# PGTNX01_teensy.net
KiCad netlist of a schematic drawn in EAGLE
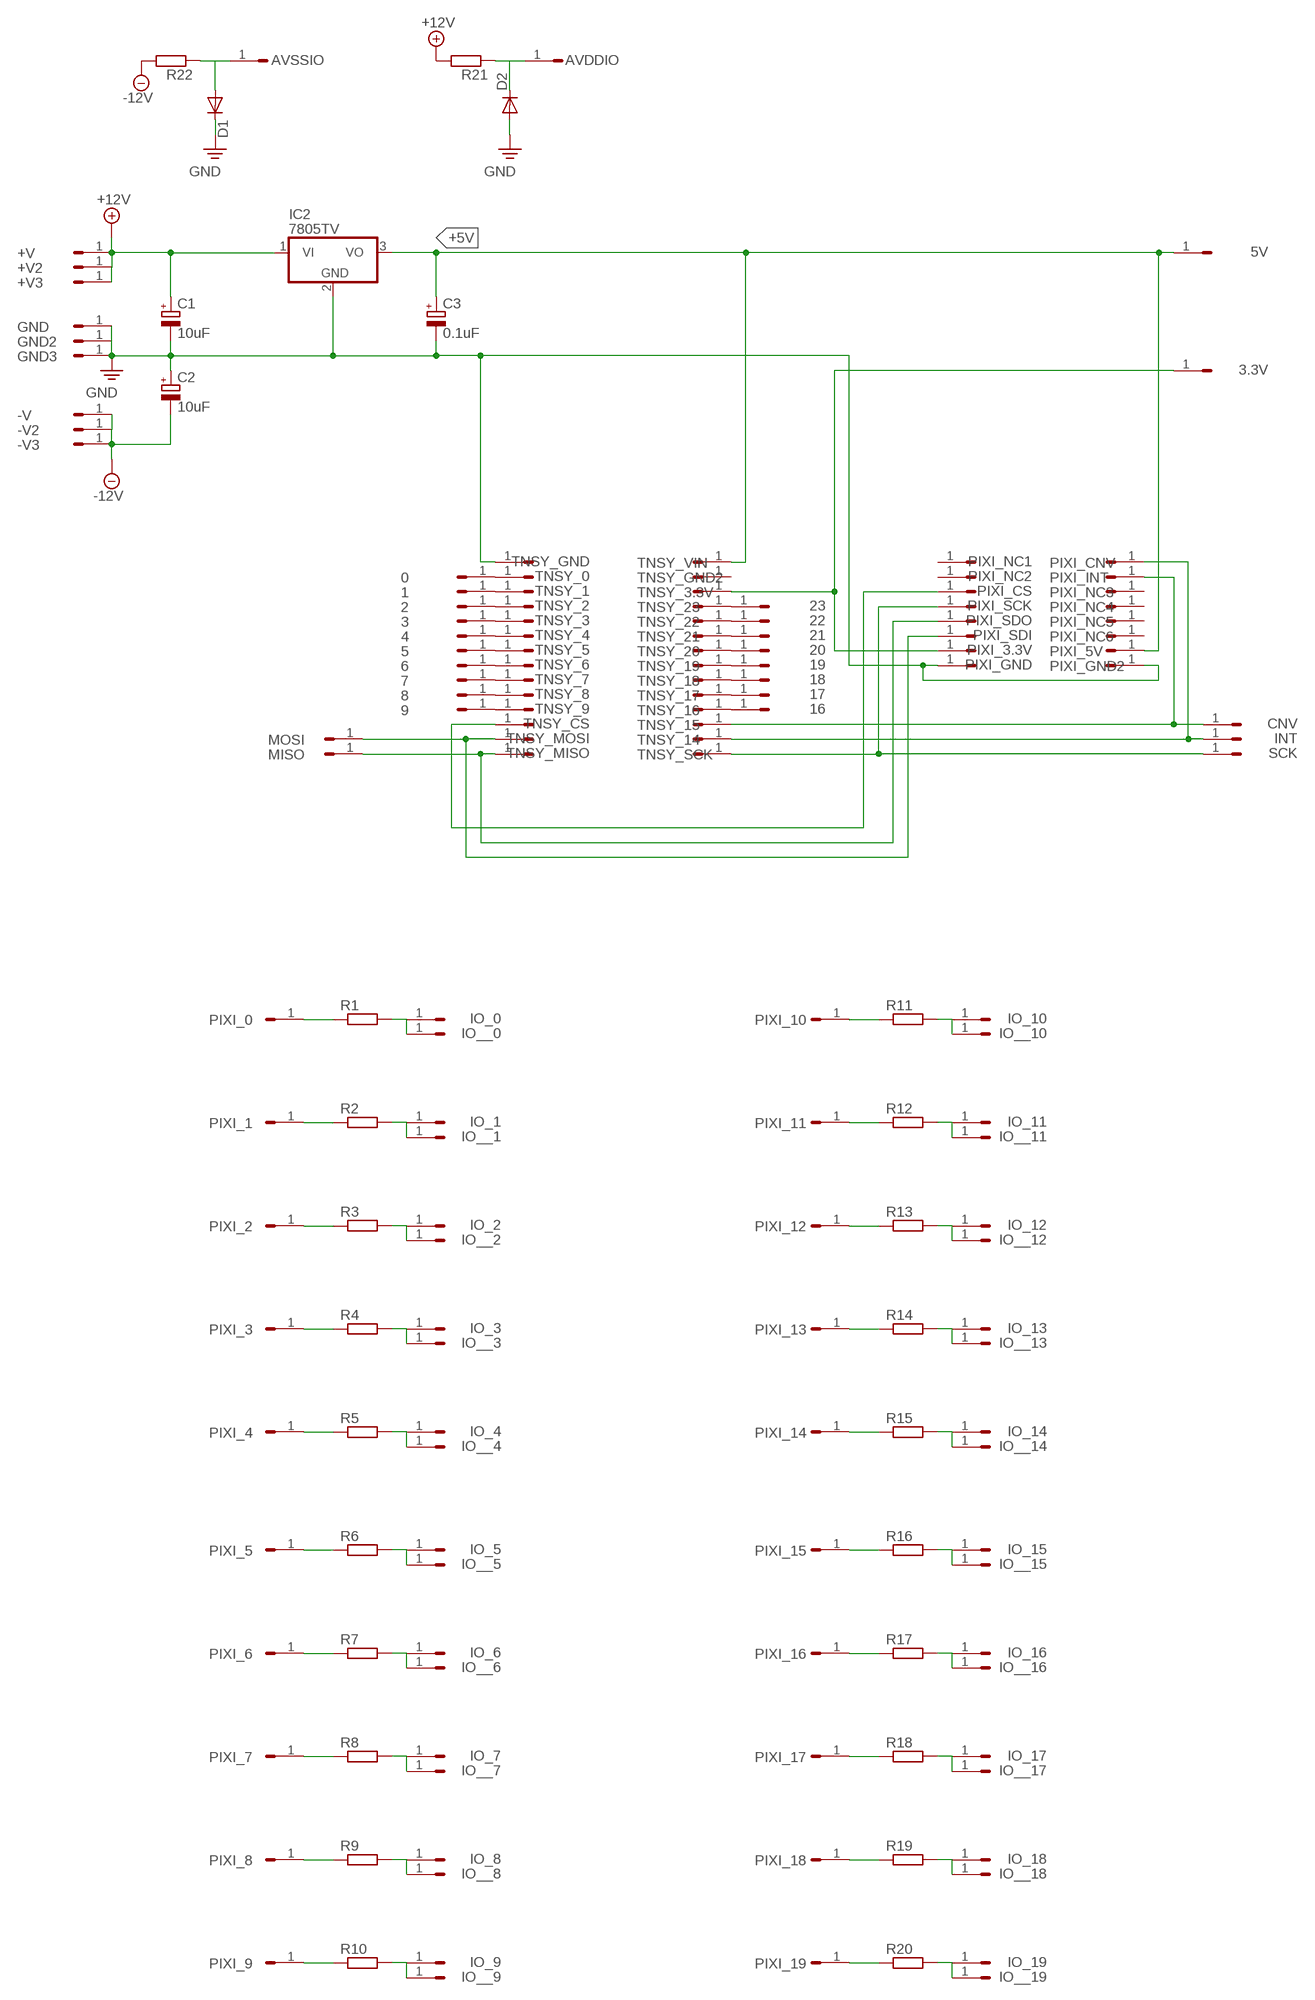
[diagram p0: schematic, sheet 1]

(export (version "E")
  (design (tool "Eeschema 10.0.6"))
  (components
    (comp (ref "+V")
      (value "HEADER/MALE/01")
      (footprint "eagle-import:HEADER_MALE_01")
      (fields (field (name "SPICEPREFIX") "X"))
      (libsource (lib "eagle-import") (part "HEADER/MALE/01"))
    )
    (comp (ref "+V2")
      (value "HEADER/MALE/01")
      (footprint "eagle-import:HEADER_MALE_01")
      (fields (field (name "SPICEPREFIX") "X"))
      (libsource (lib "eagle-import") (part "HEADER/MALE/01"))
    )
    (comp (ref "+V3")
      (value "HEADER/MALE/01")
      (footprint "eagle-import:HEADER_MALE_01")
      (fields (field (name "SPICEPREFIX") "X"))
      (libsource (lib "eagle-import") (part "HEADER/MALE/01"))
    )
    (comp (ref "-V")
      (value "HEADER/MALE/01")
      (footprint "eagle-import:HEADER_MALE_01")
      (fields (field (name "SPICEPREFIX") "X"))
      (libsource (lib "eagle-import") (part "HEADER/MALE/01"))
    )
    (comp (ref "-V2")
      (value "HEADER/MALE/01")
      (footprint "eagle-import:HEADER_MALE_01")
      (fields (field (name "SPICEPREFIX") "X"))
      (libsource (lib "eagle-import") (part "HEADER/MALE/01"))
    )
    (comp (ref "-V3")
      (value "HEADER/MALE/01")
      (footprint "eagle-import:HEADER_MALE_01")
      (fields (field (name "SPICEPREFIX") "X"))
      (libsource (lib "eagle-import") (part "HEADER/MALE/01"))
    )
    (comp (ref "0")
      (value "HEADER/MALE/01")
      (footprint "eagle-import:HEADER_MALE_01")
      (fields (field (name "SPICEPREFIX") "X"))
      (libsource (lib "eagle-import") (part "HEADER/MALE/01"))
    )
    (comp (ref "1")
      (value "HEADER/MALE/01")
      (footprint "eagle-import:HEADER_MALE_01")
      (fields (field (name "SPICEPREFIX") "X"))
      (libsource (lib "eagle-import") (part "HEADER/MALE/01"))
    )
    (comp (ref "2")
      (value "HEADER/MALE/01")
      (footprint "eagle-import:HEADER_MALE_01")
      (fields (field (name "SPICEPREFIX") "X"))
      (libsource (lib "eagle-import") (part "HEADER/MALE/01"))
    )
    (comp (ref "3")
      (value "HEADER/MALE/01")
      (footprint "eagle-import:HEADER_MALE_01")
      (fields (field (name "SPICEPREFIX") "X"))
      (libsource (lib "eagle-import") (part "HEADER/MALE/01"))
    )
    (comp (ref "3.3V")
      (value "HEADER/MALE/01")
      (footprint "eagle-import:HEADER_MALE_01")
      (fields (field (name "SPICEPREFIX") "X"))
      (libsource (lib "eagle-import") (part "HEADER/MALE/01"))
    )
    (comp (ref "4")
      (value "HEADER/MALE/01")
      (footprint "eagle-import:HEADER_MALE_01")
      (fields (field (name "SPICEPREFIX") "X"))
      (libsource (lib "eagle-import") (part "HEADER/MALE/01"))
    )
    (comp (ref "5")
      (value "HEADER/MALE/01")
      (footprint "eagle-import:HEADER_MALE_01")
      (fields (field (name "SPICEPREFIX") "X"))
      (libsource (lib "eagle-import") (part "HEADER/MALE/01"))
    )
    (comp (ref "5V")
      (value "HEADER/MALE/01")
      (footprint "eagle-import:HEADER_MALE_01")
      (fields (field (name "SPICEPREFIX") "X"))
      (libsource (lib "eagle-import") (part "HEADER/MALE/01"))
    )
    (comp (ref "6")
      (value "HEADER/MALE/01")
      (footprint "eagle-import:HEADER_MALE_01")
      (fields (field (name "SPICEPREFIX") "X"))
      (libsource (lib "eagle-import") (part "HEADER/MALE/01"))
    )
    (comp (ref "7")
      (value "HEADER/MALE/01")
      (footprint "eagle-import:HEADER_MALE_01")
      (fields (field (name "SPICEPREFIX") "X"))
      (libsource (lib "eagle-import") (part "HEADER/MALE/01"))
    )
    (comp (ref "8")
      (value "HEADER/MALE/01")
      (footprint "eagle-import:HEADER_MALE_01")
      (fields (field (name "SPICEPREFIX") "X"))
      (libsource (lib "eagle-import") (part "HEADER/MALE/01"))
    )
    (comp (ref "9")
      (value "HEADER/MALE/01")
      (footprint "eagle-import:HEADER_MALE_01")
      (fields (field (name "SPICEPREFIX") "X"))
      (libsource (lib "eagle-import") (part "HEADER/MALE/01"))
    )
    (comp (ref "16")
      (value "HEADER/MALE/01")
      (footprint "eagle-import:HEADER_MALE_01")
      (fields (field (name "SPICEPREFIX") "X"))
      (libsource (lib "eagle-import") (part "HEADER/MALE/01"))
    )
    (comp (ref "17")
      (value "HEADER/MALE/01")
      (footprint "eagle-import:HEADER_MALE_01")
      (fields (field (name "SPICEPREFIX") "X"))
      (libsource (lib "eagle-import") (part "HEADER/MALE/01"))
    )
    (comp (ref "18")
      (value "HEADER/MALE/01")
      (footprint "eagle-import:HEADER_MALE_01")
      (fields (field (name "SPICEPREFIX") "X"))
      (libsource (lib "eagle-import") (part "HEADER/MALE/01"))
    )
    (comp (ref "19")
      (value "HEADER/MALE/01")
      (footprint "eagle-import:HEADER_MALE_01")
      (fields (field (name "SPICEPREFIX") "X"))
      (libsource (lib "eagle-import") (part "HEADER/MALE/01"))
    )
    (comp (ref "20")
      (value "HEADER/MALE/01")
      (footprint "eagle-import:HEADER_MALE_01")
      (fields (field (name "SPICEPREFIX") "X"))
      (libsource (lib "eagle-import") (part "HEADER/MALE/01"))
    )
    (comp (ref "21")
      (value "HEADER/MALE/01")
      (footprint "eagle-import:HEADER_MALE_01")
      (fields (field (name "SPICEPREFIX") "X"))
      (libsource (lib "eagle-import") (part "HEADER/MALE/01"))
    )
    (comp (ref "22")
      (value "HEADER/MALE/01")
      (footprint "eagle-import:HEADER_MALE_01")
      (fields (field (name "SPICEPREFIX") "X"))
      (libsource (lib "eagle-import") (part "HEADER/MALE/01"))
    )
    (comp (ref "23")
      (value "HEADER/MALE/01")
      (footprint "eagle-import:HEADER_MALE_01")
      (fields (field (name "SPICEPREFIX") "X"))
      (libsource (lib "eagle-import") (part "HEADER/MALE/01"))
    )
    (comp (ref "AVDDIO")
      (value "HEADER/MALE/01")
      (footprint "eagle-import:HEADER_MALE_01")
      (fields (field (name "SPICEPREFIX") "X"))
      (libsource (lib "eagle-import") (part "HEADER/MALE/01"))
    )
    (comp (ref "AVSSIO")
      (value "HEADER/MALE/01")
      (footprint "eagle-import:HEADER_MALE_01")
      (fields (field (name "SPICEPREFIX") "X"))
      (libsource (lib "eagle-import") (part "HEADER/MALE/01"))
    )
    (comp (ref "C1")
      (value "10uF")
      (footprint "eagle-import:E2,5-6")
      (fields (field (name "SPICEPREFIX") "C"))
      (libsource (lib "eagle-import") (part "CAPACITOR/POLARIZEDE2.5-6"))
    )
    (comp (ref "C2")
      (value "10uF")
      (footprint "eagle-import:E2,5-6")
      (fields (field (name "SPICEPREFIX") "C"))
      (libsource (lib "eagle-import") (part "CAPACITOR/POLARIZEDE2.5-6"))
    )
    (comp (ref "C3")
      (value "0.1uF")
      (footprint "eagle-import:E2,5-6")
      (fields (field (name "SPICEPREFIX") "C"))
      (libsource (lib "eagle-import") (part "CAPACITOR/POLARIZEDE2.5-6"))
    )
    (comp (ref "CNV")
      (value "HEADER/MALE/01")
      (footprint "eagle-import:HEADER_MALE_01")
      (fields (field (name "SPICEPREFIX") "X"))
      (libsource (lib "eagle-import") (part "HEADER/MALE/01"))
    )
    (comp (ref "D1")
      (value "1N4148DO35-7")
      (footprint "eagle-import:DO35-7")
      (libsource (lib "eagle-import") (part "1N4148DO35-7"))
    )
    (comp (ref "D2")
      (value "1N4148DO35-7")
      (footprint "eagle-import:DO35-7")
      (libsource (lib "eagle-import") (part "1N4148DO35-7"))
    )
    (comp (ref "GND")
      (value "HEADER/MALE/01")
      (footprint "eagle-import:HEADER_MALE_01")
      (fields (field (name "SPICEPREFIX") "X"))
      (libsource (lib "eagle-import") (part "HEADER/MALE/01"))
    )
    (comp (ref "GND2")
      (value "HEADER/MALE/01")
      (footprint "eagle-import:HEADER_MALE_01")
      (fields (field (name "SPICEPREFIX") "X"))
      (libsource (lib "eagle-import") (part "HEADER/MALE/01"))
    )
    (comp (ref "GND3")
      (value "HEADER/MALE/01")
      (footprint "eagle-import:HEADER_MALE_01")
      (fields (field (name "SPICEPREFIX") "X"))
      (libsource (lib "eagle-import") (part "HEADER/MALE/01"))
    )
    (comp (ref "IC2")
      (value "7805TV")
      (footprint "eagle-import:TO220V")
      (libsource (lib "eagle-import") (part "78TV05"))
    )
    (comp (ref "INT")
      (value "HEADER/MALE/01")
      (footprint "eagle-import:HEADER_MALE_01")
      (fields (field (name "SPICEPREFIX") "X"))
      (libsource (lib "eagle-import") (part "HEADER/MALE/01"))
    )
    (comp (ref "IO_0")
      (value "HEADER/MALE/01")
      (footprint "eagle-import:HEADER_MALE_01")
      (fields (field (name "SPICEPREFIX") "X"))
      (libsource (lib "eagle-import") (part "HEADER/MALE/01"))
    )
    (comp (ref "IO_1")
      (value "HEADER/MALE/01")
      (footprint "eagle-import:HEADER_MALE_01")
      (fields (field (name "SPICEPREFIX") "X"))
      (libsource (lib "eagle-import") (part "HEADER/MALE/01"))
    )
    (comp (ref "IO_2")
      (value "HEADER/MALE/01")
      (footprint "eagle-import:HEADER_MALE_01")
      (fields (field (name "SPICEPREFIX") "X"))
      (libsource (lib "eagle-import") (part "HEADER/MALE/01"))
    )
    (comp (ref "IO_3")
      (value "HEADER/MALE/01")
      (footprint "eagle-import:HEADER_MALE_01")
      (fields (field (name "SPICEPREFIX") "X"))
      (libsource (lib "eagle-import") (part "HEADER/MALE/01"))
    )
    (comp (ref "IO_4")
      (value "HEADER/MALE/01")
      (footprint "eagle-import:HEADER_MALE_01")
      (fields (field (name "SPICEPREFIX") "X"))
      (libsource (lib "eagle-import") (part "HEADER/MALE/01"))
    )
    (comp (ref "IO_5")
      (value "HEADER/MALE/01")
      (footprint "eagle-import:HEADER_MALE_01")
      (fields (field (name "SPICEPREFIX") "X"))
      (libsource (lib "eagle-import") (part "HEADER/MALE/01"))
    )
    (comp (ref "IO_6")
      (value "HEADER/MALE/01")
      (footprint "eagle-import:HEADER_MALE_01")
      (fields (field (name "SPICEPREFIX") "X"))
      (libsource (lib "eagle-import") (part "HEADER/MALE/01"))
    )
    (comp (ref "IO_7")
      (value "HEADER/MALE/01")
      (footprint "eagle-import:HEADER_MALE_01")
      (fields (field (name "SPICEPREFIX") "X"))
      (libsource (lib "eagle-import") (part "HEADER/MALE/01"))
    )
    (comp (ref "IO_8")
      (value "HEADER/MALE/01")
      (footprint "eagle-import:HEADER_MALE_01")
      (fields (field (name "SPICEPREFIX") "X"))
      (libsource (lib "eagle-import") (part "HEADER/MALE/01"))
    )
    (comp (ref "IO_9")
      (value "HEADER/MALE/01")
      (footprint "eagle-import:HEADER_MALE_01")
      (fields (field (name "SPICEPREFIX") "X"))
      (libsource (lib "eagle-import") (part "HEADER/MALE/01"))
    )
    (comp (ref "IO_10")
      (value "HEADER/MALE/01")
      (footprint "eagle-import:HEADER_MALE_01")
      (fields (field (name "SPICEPREFIX") "X"))
      (libsource (lib "eagle-import") (part "HEADER/MALE/01"))
    )
    (comp (ref "IO_11")
      (value "HEADER/MALE/01")
      (footprint "eagle-import:HEADER_MALE_01")
      (fields (field (name "SPICEPREFIX") "X"))
      (libsource (lib "eagle-import") (part "HEADER/MALE/01"))
    )
    (comp (ref "IO_12")
      (value "HEADER/MALE/01")
      (footprint "eagle-import:HEADER_MALE_01")
      (fields (field (name "SPICEPREFIX") "X"))
      (libsource (lib "eagle-import") (part "HEADER/MALE/01"))
    )
    (comp (ref "IO_13")
      (value "HEADER/MALE/01")
      (footprint "eagle-import:HEADER_MALE_01")
      (fields (field (name "SPICEPREFIX") "X"))
      (libsource (lib "eagle-import") (part "HEADER/MALE/01"))
    )
    (comp (ref "IO_14")
      (value "HEADER/MALE/01")
      (footprint "eagle-import:HEADER_MALE_01")
      (fields (field (name "SPICEPREFIX") "X"))
      (libsource (lib "eagle-import") (part "HEADER/MALE/01"))
    )
    (comp (ref "IO_15")
      (value "HEADER/MALE/01")
      (footprint "eagle-import:HEADER_MALE_01")
      (fields (field (name "SPICEPREFIX") "X"))
      (libsource (lib "eagle-import") (part "HEADER/MALE/01"))
    )
    (comp (ref "IO_16")
      (value "HEADER/MALE/01")
      (footprint "eagle-import:HEADER_MALE_01")
      (fields (field (name "SPICEPREFIX") "X"))
      (libsource (lib "eagle-import") (part "HEADER/MALE/01"))
    )
    (comp (ref "IO_17")
      (value "HEADER/MALE/01")
      (footprint "eagle-import:HEADER_MALE_01")
      (fields (field (name "SPICEPREFIX") "X"))
      (libsource (lib "eagle-import") (part "HEADER/MALE/01"))
    )
    (comp (ref "IO_18")
      (value "HEADER/MALE/01")
      (footprint "eagle-import:HEADER_MALE_01")
      (fields (field (name "SPICEPREFIX") "X"))
      (libsource (lib "eagle-import") (part "HEADER/MALE/01"))
    )
    (comp (ref "IO_19")
      (value "HEADER/MALE/01")
      (footprint "eagle-import:HEADER_MALE_01")
      (fields (field (name "SPICEPREFIX") "X"))
      (libsource (lib "eagle-import") (part "HEADER/MALE/01"))
    )
    (comp (ref "IO__0")
      (value "HEADER/MALE/01")
      (footprint "eagle-import:HEADER_MALE_01")
      (fields (field (name "SPICEPREFIX") "X"))
      (libsource (lib "eagle-import") (part "HEADER/MALE/01"))
    )
    (comp (ref "IO__1")
      (value "HEADER/MALE/01")
      (footprint "eagle-import:HEADER_MALE_01")
      (fields (field (name "SPICEPREFIX") "X"))
      (libsource (lib "eagle-import") (part "HEADER/MALE/01"))
    )
    (comp (ref "IO__2")
      (value "HEADER/MALE/01")
      (footprint "eagle-import:HEADER_MALE_01")
      (fields (field (name "SPICEPREFIX") "X"))
      (libsource (lib "eagle-import") (part "HEADER/MALE/01"))
    )
    (comp (ref "IO__3")
      (value "HEADER/MALE/01")
      (footprint "eagle-import:HEADER_MALE_01")
      (fields (field (name "SPICEPREFIX") "X"))
      (libsource (lib "eagle-import") (part "HEADER/MALE/01"))
    )
    (comp (ref "IO__4")
      (value "HEADER/MALE/01")
      (footprint "eagle-import:HEADER_MALE_01")
      (fields (field (name "SPICEPREFIX") "X"))
      (libsource (lib "eagle-import") (part "HEADER/MALE/01"))
    )
    (comp (ref "IO__5")
      (value "HEADER/MALE/01")
      (footprint "eagle-import:HEADER_MALE_01")
      (fields (field (name "SPICEPREFIX") "X"))
      (libsource (lib "eagle-import") (part "HEADER/MALE/01"))
    )
    (comp (ref "IO__6")
      (value "HEADER/MALE/01")
      (footprint "eagle-import:HEADER_MALE_01")
      (fields (field (name "SPICEPREFIX") "X"))
      (libsource (lib "eagle-import") (part "HEADER/MALE/01"))
    )
    (comp (ref "IO__7")
      (value "HEADER/MALE/01")
      (footprint "eagle-import:HEADER_MALE_01")
      (fields (field (name "SPICEPREFIX") "X"))
      (libsource (lib "eagle-import") (part "HEADER/MALE/01"))
    )
    (comp (ref "IO__8")
      (value "HEADER/MALE/01")
      (footprint "eagle-import:HEADER_MALE_01")
      (fields (field (name "SPICEPREFIX") "X"))
      (libsource (lib "eagle-import") (part "HEADER/MALE/01"))
    )
    (comp (ref "IO__9")
      (value "HEADER/MALE/01")
      (footprint "eagle-import:HEADER_MALE_01")
      (fields (field (name "SPICEPREFIX") "X"))
      (libsource (lib "eagle-import") (part "HEADER/MALE/01"))
    )
    (comp (ref "IO__10")
      (value "HEADER/MALE/01")
      (footprint "eagle-import:HEADER_MALE_01")
      (fields (field (name "SPICEPREFIX") "X"))
      (libsource (lib "eagle-import") (part "HEADER/MALE/01"))
    )
    (comp (ref "IO__11")
      (value "HEADER/MALE/01")
      (footprint "eagle-import:HEADER_MALE_01")
      (fields (field (name "SPICEPREFIX") "X"))
      (libsource (lib "eagle-import") (part "HEADER/MALE/01"))
    )
    (comp (ref "IO__12")
      (value "HEADER/MALE/01")
      (footprint "eagle-import:HEADER_MALE_01")
      (fields (field (name "SPICEPREFIX") "X"))
      (libsource (lib "eagle-import") (part "HEADER/MALE/01"))
    )
    (comp (ref "IO__13")
      (value "HEADER/MALE/01")
      (footprint "eagle-import:HEADER_MALE_01")
      (fields (field (name "SPICEPREFIX") "X"))
      (libsource (lib "eagle-import") (part "HEADER/MALE/01"))
    )
    (comp (ref "IO__14")
      (value "HEADER/MALE/01")
      (footprint "eagle-import:HEADER_MALE_01")
      (fields (field (name "SPICEPREFIX") "X"))
      (libsource (lib "eagle-import") (part "HEADER/MALE/01"))
    )
    (comp (ref "IO__15")
      (value "HEADER/MALE/01")
      (footprint "eagle-import:HEADER_MALE_01")
      (fields (field (name "SPICEPREFIX") "X"))
      (libsource (lib "eagle-import") (part "HEADER/MALE/01"))
    )
    (comp (ref "IO__16")
      (value "HEADER/MALE/01")
      (footprint "eagle-import:HEADER_MALE_01")
      (fields (field (name "SPICEPREFIX") "X"))
      (libsource (lib "eagle-import") (part "HEADER/MALE/01"))
    )
    (comp (ref "IO__17")
      (value "HEADER/MALE/01")
      (footprint "eagle-import:HEADER_MALE_01")
      (fields (field (name "SPICEPREFIX") "X"))
      (libsource (lib "eagle-import") (part "HEADER/MALE/01"))
    )
    (comp (ref "IO__18")
      (value "HEADER/MALE/01")
      (footprint "eagle-import:HEADER_MALE_01")
      (fields (field (name "SPICEPREFIX") "X"))
      (libsource (lib "eagle-import") (part "HEADER/MALE/01"))
    )
    (comp (ref "IO__19")
      (value "HEADER/MALE/01")
      (footprint "eagle-import:HEADER_MALE_01")
      (fields (field (name "SPICEPREFIX") "X"))
      (libsource (lib "eagle-import") (part "HEADER/MALE/01"))
    )
    (comp (ref "MISO")
      (value "HEADER/MALE/01")
      (footprint "eagle-import:HEADER_MALE_01")
      (fields (field (name "SPICEPREFIX") "X"))
      (libsource (lib "eagle-import") (part "HEADER/MALE/01"))
    )
    (comp (ref "MOSI")
      (value "HEADER/MALE/01")
      (footprint "eagle-import:HEADER_MALE_01")
      (fields (field (name "SPICEPREFIX") "X"))
      (libsource (lib "eagle-import") (part "HEADER/MALE/01"))
    )
    (comp (ref "PIXI_0")
      (value "HEADER/MALE/01")
      (footprint "eagle-import:HEADER_MALE_01")
      (fields (field (name "SPICEPREFIX") "X"))
      (libsource (lib "eagle-import") (part "HEADER/MALE/01"))
    )
    (comp (ref "PIXI_1")
      (value "HEADER/MALE/01")
      (footprint "eagle-import:HEADER_MALE_01")
      (fields (field (name "SPICEPREFIX") "X"))
      (libsource (lib "eagle-import") (part "HEADER/MALE/01"))
    )
    (comp (ref "PIXI_2")
      (value "HEADER/MALE/01")
      (footprint "eagle-import:HEADER_MALE_01")
      (fields (field (name "SPICEPREFIX") "X"))
      (libsource (lib "eagle-import") (part "HEADER/MALE/01"))
    )
    (comp (ref "PIXI_3")
      (value "HEADER/MALE/01")
      (footprint "eagle-import:HEADER_MALE_01")
      (fields (field (name "SPICEPREFIX") "X"))
      (libsource (lib "eagle-import") (part "HEADER/MALE/01"))
    )
    (comp (ref "PIXI_3.3V")
      (value "HEADER/MALE/01")
      (footprint "eagle-import:HEADER_MALE_01")
      (fields (field (name "SPICEPREFIX") "X"))
      (libsource (lib "eagle-import") (part "HEADER/MALE/01"))
    )
    (comp (ref "PIXI_4")
      (value "HEADER/MALE/01")
      (footprint "eagle-import:HEADER_MALE_01")
      (fields (field (name "SPICEPREFIX") "X"))
      (libsource (lib "eagle-import") (part "HEADER/MALE/01"))
    )
    (comp (ref "PIXI_5")
      (value "HEADER/MALE/01")
      (footprint "eagle-import:HEADER_MALE_01")
      (fields (field (name "SPICEPREFIX") "X"))
      (libsource (lib "eagle-import") (part "HEADER/MALE/01"))
    )
    (comp (ref "PIXI_5V")
      (value "HEADER/MALE/01")
      (footprint "eagle-import:HEADER_MALE_01")
      (fields (field (name "SPICEPREFIX") "X"))
      (libsource (lib "eagle-import") (part "HEADER/MALE/01"))
    )
    (comp (ref "PIXI_6")
      (value "HEADER/MALE/01")
      (footprint "eagle-import:HEADER_MALE_01")
      (fields (field (name "SPICEPREFIX") "X"))
      (libsource (lib "eagle-import") (part "HEADER/MALE/01"))
    )
    (comp (ref "PIXI_7")
      (value "HEADER/MALE/01")
      (footprint "eagle-import:HEADER_MALE_01")
      (fields (field (name "SPICEPREFIX") "X"))
      (libsource (lib "eagle-import") (part "HEADER/MALE/01"))
    )
    (comp (ref "PIXI_8")
      (value "HEADER/MALE/01")
      (footprint "eagle-import:HEADER_MALE_01")
      (fields (field (name "SPICEPREFIX") "X"))
      (libsource (lib "eagle-import") (part "HEADER/MALE/01"))
    )
    (comp (ref "PIXI_9")
      (value "HEADER/MALE/01")
      (footprint "eagle-import:HEADER_MALE_01")
      (fields (field (name "SPICEPREFIX") "X"))
      (libsource (lib "eagle-import") (part "HEADER/MALE/01"))
    )
    (comp (ref "PIXI_10")
      (value "HEADER/MALE/01")
      (footprint "eagle-import:HEADER_MALE_01")
      (fields (field (name "SPICEPREFIX") "X"))
      (libsource (lib "eagle-import") (part "HEADER/MALE/01"))
    )
    (comp (ref "PIXI_11")
      (value "HEADER/MALE/01")
      (footprint "eagle-import:HEADER_MALE_01")
      (fields (field (name "SPICEPREFIX") "X"))
      (libsource (lib "eagle-import") (part "HEADER/MALE/01"))
    )
    (comp (ref "PIXI_12")
      (value "HEADER/MALE/01")
      (footprint "eagle-import:HEADER_MALE_01")
      (fields (field (name "SPICEPREFIX") "X"))
      (libsource (lib "eagle-import") (part "HEADER/MALE/01"))
    )
    (comp (ref "PIXI_13")
      (value "HEADER/MALE/01")
      (footprint "eagle-import:HEADER_MALE_01")
      (fields (field (name "SPICEPREFIX") "X"))
      (libsource (lib "eagle-import") (part "HEADER/MALE/01"))
    )
    (comp (ref "PIXI_14")
      (value "HEADER/MALE/01")
      (footprint "eagle-import:HEADER_MALE_01")
      (fields (field (name "SPICEPREFIX") "X"))
      (libsource (lib "eagle-import") (part "HEADER/MALE/01"))
    )
    (comp (ref "PIXI_15")
      (value "HEADER/MALE/01")
      (footprint "eagle-import:HEADER_MALE_01")
      (fields (field (name "SPICEPREFIX") "X"))
      (libsource (lib "eagle-import") (part "HEADER/MALE/01"))
    )
    (comp (ref "PIXI_16")
      (value "HEADER/MALE/01")
      (footprint "eagle-import:HEADER_MALE_01")
      (fields (field (name "SPICEPREFIX") "X"))
      (libsource (lib "eagle-import") (part "HEADER/MALE/01"))
    )
    (comp (ref "PIXI_17")
      (value "HEADER/MALE/01")
      (footprint "eagle-import:HEADER_MALE_01")
      (fields (field (name "SPICEPREFIX") "X"))
      (libsource (lib "eagle-import") (part "HEADER/MALE/01"))
    )
    (comp (ref "PIXI_18")
      (value "HEADER/MALE/01")
      (footprint "eagle-import:HEADER_MALE_01")
      (fields (field (name "SPICEPREFIX") "X"))
      (libsource (lib "eagle-import") (part "HEADER/MALE/01"))
    )
    (comp (ref "PIXI_19")
      (value "HEADER/MALE/01")
      (footprint "eagle-import:HEADER_MALE_01")
      (fields (field (name "SPICEPREFIX") "X"))
      (libsource (lib "eagle-import") (part "HEADER/MALE/01"))
    )
    (comp (ref "PIXI_CNV")
      (value "HEADER/MALE/01")
      (footprint "eagle-import:HEADER_MALE_01")
      (fields (field (name "SPICEPREFIX") "X"))
      (libsource (lib "eagle-import") (part "HEADER/MALE/01"))
    )
    (comp (ref "PIXI_CS")
      (value "HEADER/MALE/01")
      (footprint "eagle-import:HEADER_MALE_01")
      (fields (field (name "SPICEPREFIX") "X"))
      (libsource (lib "eagle-import") (part "HEADER/MALE/01"))
    )
    (comp (ref "PIXI_GND")
      (value "HEADER/MALE/01")
      (footprint "eagle-import:HEADER_MALE_01")
      (fields (field (name "SPICEPREFIX") "X"))
      (libsource (lib "eagle-import") (part "HEADER/MALE/01"))
    )
    (comp (ref "PIXI_GND2")
      (value "HEADER/MALE/01")
      (footprint "eagle-import:HEADER_MALE_01")
      (fields (field (name "SPICEPREFIX") "X"))
      (libsource (lib "eagle-import") (part "HEADER/MALE/01"))
    )
    (comp (ref "PIXI_INT")
      (value "HEADER/MALE/01")
      (footprint "eagle-import:HEADER_MALE_01")
      (fields (field (name "SPICEPREFIX") "X"))
      (libsource (lib "eagle-import") (part "HEADER/MALE/01"))
    )
    (comp (ref "PIXI_NC1")
      (value "HEADER/MALE/01")
      (footprint "eagle-import:HEADER_MALE_01")
      (fields (field (name "SPICEPREFIX") "X"))
      (libsource (lib "eagle-import") (part "HEADER/MALE/01"))
    )
    (comp (ref "PIXI_NC2")
      (value "HEADER/MALE/01")
      (footprint "eagle-import:HEADER_MALE_01")
      (fields (field (name "SPICEPREFIX") "X"))
      (libsource (lib "eagle-import") (part "HEADER/MALE/01"))
    )
    (comp (ref "PIXI_NC3")
      (value "HEADER/MALE/01")
      (footprint "eagle-import:HEADER_MALE_01")
      (fields (field (name "SPICEPREFIX") "X"))
      (libsource (lib "eagle-import") (part "HEADER/MALE/01"))
    )
    (comp (ref "PIXI_NC4")
      (value "HEADER/MALE/01")
      (footprint "eagle-import:HEADER_MALE_01")
      (fields (field (name "SPICEPREFIX") "X"))
      (libsource (lib "eagle-import") (part "HEADER/MALE/01"))
    )
    (comp (ref "PIXI_NC5")
      (value "HEADER/MALE/01")
      (footprint "eagle-import:HEADER_MALE_01")
      (fields (field (name "SPICEPREFIX") "X"))
      (libsource (lib "eagle-import") (part "HEADER/MALE/01"))
    )
    (comp (ref "PIXI_NC6")
      (value "HEADER/MALE/01")
      (footprint "eagle-import:HEADER_MALE_01")
      (fields (field (name "SPICEPREFIX") "X"))
      (libsource (lib "eagle-import") (part "HEADER/MALE/01"))
    )
    (comp (ref "PIXI_SCK")
      (value "HEADER/MALE/01")
      (footprint "eagle-import:HEADER_MALE_01")
      (fields (field (name "SPICEPREFIX") "X"))
      (libsource (lib "eagle-import") (part "HEADER/MALE/01"))
    )
    (comp (ref "PIXI_SDI")
      (value "HEADER/MALE/01")
      (footprint "eagle-import:HEADER_MALE_01")
      (fields (field (name "SPICEPREFIX") "X"))
      (libsource (lib "eagle-import") (part "HEADER/MALE/01"))
    )
    (comp (ref "PIXI_SDO")
      (value "HEADER/MALE/01")
      (footprint "eagle-import:HEADER_MALE_01")
      (fields (field (name "SPICEPREFIX") "X"))
      (libsource (lib "eagle-import") (part "HEADER/MALE/01"))
    )
    (comp (ref "R1")
      (value "RESISTORRESISTOR/UPRIGHT/7.5")
      (footprint "eagle-import:RESISTOR_7.5")
      (libsource (lib "eagle-import") (part "RESISTORRESISTOR/UPRIGHT/7.5"))
    )
    (comp (ref "R2")
      (value "RESISTORRESISTOR/UPRIGHT/7.5")
      (footprint "eagle-import:RESISTOR_7.5")
      (libsource (lib "eagle-import") (part "RESISTORRESISTOR/UPRIGHT/7.5"))
    )
    (comp (ref "R3")
      (value "RESISTORRESISTOR/UPRIGHT/7.5")
      (footprint "eagle-import:RESISTOR_7.5")
      (libsource (lib "eagle-import") (part "RESISTORRESISTOR/UPRIGHT/7.5"))
    )
    (comp (ref "R4")
      (value "RESISTORRESISTOR/UPRIGHT/7.5")
      (footprint "eagle-import:RESISTOR_7.5")
      (libsource (lib "eagle-import") (part "RESISTORRESISTOR/UPRIGHT/7.5"))
    )
    (comp (ref "R5")
      (value "RESISTORRESISTOR/UPRIGHT/7.5")
      (footprint "eagle-import:RESISTOR_7.5")
      (libsource (lib "eagle-import") (part "RESISTORRESISTOR/UPRIGHT/7.5"))
    )
    (comp (ref "R6")
      (value "RESISTORRESISTOR/UPRIGHT/7.5")
      (footprint "eagle-import:RESISTOR_7.5")
      (libsource (lib "eagle-import") (part "RESISTORRESISTOR/UPRIGHT/7.5"))
    )
    (comp (ref "R7")
      (value "RESISTORRESISTOR/UPRIGHT/7.5")
      (footprint "eagle-import:RESISTOR_7.5")
      (libsource (lib "eagle-import") (part "RESISTORRESISTOR/UPRIGHT/7.5"))
    )
    (comp (ref "R8")
      (value "RESISTORRESISTOR/UPRIGHT/7.5")
      (footprint "eagle-import:RESISTOR_7.5")
      (libsource (lib "eagle-import") (part "RESISTORRESISTOR/UPRIGHT/7.5"))
    )
    (comp (ref "R9")
      (value "RESISTORRESISTOR/UPRIGHT/7.5")
      (footprint "eagle-import:RESISTOR_7.5")
      (libsource (lib "eagle-import") (part "RESISTORRESISTOR/UPRIGHT/7.5"))
    )
    (comp (ref "R10")
      (value "RESISTORRESISTOR/UPRIGHT/7.5")
      (footprint "eagle-import:RESISTOR_7.5")
      (libsource (lib "eagle-import") (part "RESISTORRESISTOR/UPRIGHT/7.5"))
    )
    (comp (ref "R11")
      (value "RESISTORRESISTOR/UPRIGHT/7.5")
      (footprint "eagle-import:RESISTOR_7.5")
      (libsource (lib "eagle-import") (part "RESISTORRESISTOR/UPRIGHT/7.5"))
    )
    (comp (ref "R12")
      (value "RESISTORRESISTOR/UPRIGHT/7.5")
      (footprint "eagle-import:RESISTOR_7.5")
      (libsource (lib "eagle-import") (part "RESISTORRESISTOR/UPRIGHT/7.5"))
    )
    (comp (ref "R13")
      (value "RESISTORRESISTOR/UPRIGHT/7.5")
      (footprint "eagle-import:RESISTOR_7.5")
      (libsource (lib "eagle-import") (part "RESISTORRESISTOR/UPRIGHT/7.5"))
    )
    (comp (ref "R14")
      (value "RESISTORRESISTOR/UPRIGHT/7.5")
      (footprint "eagle-import:RESISTOR_7.5")
      (libsource (lib "eagle-import") (part "RESISTORRESISTOR/UPRIGHT/7.5"))
    )
    (comp (ref "R15")
      (value "RESISTORRESISTOR/UPRIGHT/7.5")
      (footprint "eagle-import:RESISTOR_7.5")
      (libsource (lib "eagle-import") (part "RESISTORRESISTOR/UPRIGHT/7.5"))
    )
    (comp (ref "R16")
      (value "RESISTORRESISTOR/UPRIGHT/7.5")
      (footprint "eagle-import:RESISTOR_7.5")
      (libsource (lib "eagle-import") (part "RESISTORRESISTOR/UPRIGHT/7.5"))
    )
    (comp (ref "R17")
      (value "RESISTORRESISTOR/UPRIGHT/7.5")
      (footprint "eagle-import:RESISTOR_7.5")
      (libsource (lib "eagle-import") (part "RESISTORRESISTOR/UPRIGHT/7.5"))
    )
    (comp (ref "R18")
      (value "RESISTORRESISTOR/UPRIGHT/7.5")
      (footprint "eagle-import:RESISTOR_7.5")
      (libsource (lib "eagle-import") (part "RESISTORRESISTOR/UPRIGHT/7.5"))
    )
    (comp (ref "R19")
      (value "RESISTORRESISTOR/UPRIGHT/7.5")
      (footprint "eagle-import:RESISTOR_7.5")
      (libsource (lib "eagle-import") (part "RESISTORRESISTOR/UPRIGHT/7.5"))
    )
    (comp (ref "R20")
      (value "RESISTORRESISTOR/UPRIGHT/7.5")
      (footprint "eagle-import:RESISTOR_7.5")
      (libsource (lib "eagle-import") (part "RESISTORRESISTOR/UPRIGHT/7.5"))
    )
    (comp (ref "R21")
      (value "RESISTORRESISTOR/UPRIGHT/7.5")
      (footprint "eagle-import:RESISTOR_7.5")
      (libsource (lib "eagle-import") (part "RESISTORRESISTOR/UPRIGHT/7.5"))
    )
    (comp (ref "R22")
      (value "RESISTORRESISTOR/UPRIGHT/7.5")
      (footprint "eagle-import:RESISTOR_7.5")
      (libsource (lib "eagle-import") (part "RESISTORRESISTOR/UPRIGHT/7.5"))
    )
    (comp (ref "SCK")
      (value "HEADER/MALE/01")
      (footprint "eagle-import:HEADER_MALE_01")
      (fields (field (name "SPICEPREFIX") "X"))
      (libsource (lib "eagle-import") (part "HEADER/MALE/01"))
    )
    (comp (ref "TNSY_0")
      (value "HEADER/MALE/01")
      (footprint "eagle-import:HEADER_MALE_01")
      (fields (field (name "SPICEPREFIX") "X"))
      (libsource (lib "eagle-import") (part "HEADER/MALE/01"))
    )
    (comp (ref "TNSY_1")
      (value "HEADER/MALE/01")
      (footprint "eagle-import:HEADER_MALE_01")
      (fields (field (name "SPICEPREFIX") "X"))
      (libsource (lib "eagle-import") (part "HEADER/MALE/01"))
    )
    (comp (ref "TNSY_2")
      (value "HEADER/MALE/01")
      (footprint "eagle-import:HEADER_MALE_01")
      (fields (field (name "SPICEPREFIX") "X"))
      (libsource (lib "eagle-import") (part "HEADER/MALE/01"))
    )
    (comp (ref "TNSY_3")
      (value "HEADER/MALE/01")
      (footprint "eagle-import:HEADER_MALE_01")
      (fields (field (name "SPICEPREFIX") "X"))
      (libsource (lib "eagle-import") (part "HEADER/MALE/01"))
    )
    (comp (ref "TNSY_3.3V")
      (value "HEADER/MALE/01")
      (footprint "eagle-import:HEADER_MALE_01")
      (fields (field (name "SPICEPREFIX") "X"))
      (libsource (lib "eagle-import") (part "HEADER/MALE/01"))
    )
    (comp (ref "TNSY_4")
      (value "HEADER/MALE/01")
      (footprint "eagle-import:HEADER_MALE_01")
      (fields (field (name "SPICEPREFIX") "X"))
      (libsource (lib "eagle-import") (part "HEADER/MALE/01"))
    )
    (comp (ref "TNSY_5")
      (value "HEADER/MALE/01")
      (footprint "eagle-import:HEADER_MALE_01")
      (fields (field (name "SPICEPREFIX") "X"))
      (libsource (lib "eagle-import") (part "HEADER/MALE/01"))
    )
    (comp (ref "TNSY_6")
      (value "HEADER/MALE/01")
      (footprint "eagle-import:HEADER_MALE_01")
      (fields (field (name "SPICEPREFIX") "X"))
      (libsource (lib "eagle-import") (part "HEADER/MALE/01"))
    )
    (comp (ref "TNSY_7")
      (value "HEADER/MALE/01")
      (footprint "eagle-import:HEADER_MALE_01")
      (fields (field (name "SPICEPREFIX") "X"))
      (libsource (lib "eagle-import") (part "HEADER/MALE/01"))
    )
    (comp (ref "TNSY_8")
      (value "HEADER/MALE/01")
      (footprint "eagle-import:HEADER_MALE_01")
      (fields (field (name "SPICEPREFIX") "X"))
      (libsource (lib "eagle-import") (part "HEADER/MALE/01"))
    )
    (comp (ref "TNSY_9")
      (value "HEADER/MALE/01")
      (footprint "eagle-import:HEADER_MALE_01")
      (fields (field (name "SPICEPREFIX") "X"))
      (libsource (lib "eagle-import") (part "HEADER/MALE/01"))
    )
    (comp (ref "TNSY_14")
      (value "HEADER/MALE/01")
      (footprint "eagle-import:HEADER_MALE_01")
      (fields (field (name "SPICEPREFIX") "X"))
      (libsource (lib "eagle-import") (part "HEADER/MALE/01"))
    )
    (comp (ref "TNSY_15")
      (value "HEADER/MALE/01")
      (footprint "eagle-import:HEADER_MALE_01")
      (fields (field (name "SPICEPREFIX") "X"))
      (libsource (lib "eagle-import") (part "HEADER/MALE/01"))
    )
    (comp (ref "TNSY_16")
      (value "HEADER/MALE/01")
      (footprint "eagle-import:HEADER_MALE_01")
      (fields (field (name "SPICEPREFIX") "X"))
      (libsource (lib "eagle-import") (part "HEADER/MALE/01"))
    )
    (comp (ref "TNSY_17")
      (value "HEADER/MALE/01")
      (footprint "eagle-import:HEADER_MALE_01")
      (fields (field (name "SPICEPREFIX") "X"))
      (libsource (lib "eagle-import") (part "HEADER/MALE/01"))
    )
    (comp (ref "TNSY_18")
      (value "HEADER/MALE/01")
      (footprint "eagle-import:HEADER_MALE_01")
      (fields (field (name "SPICEPREFIX") "X"))
      (libsource (lib "eagle-import") (part "HEADER/MALE/01"))
    )
    (comp (ref "TNSY_19")
      (value "HEADER/MALE/01")
      (footprint "eagle-import:HEADER_MALE_01")
      (fields (field (name "SPICEPREFIX") "X"))
      (libsource (lib "eagle-import") (part "HEADER/MALE/01"))
    )
    (comp (ref "TNSY_20")
      (value "HEADER/MALE/01")
      (footprint "eagle-import:HEADER_MALE_01")
      (fields (field (name "SPICEPREFIX") "X"))
      (libsource (lib "eagle-import") (part "HEADER/MALE/01"))
    )
    (comp (ref "TNSY_21")
      (value "HEADER/MALE/01")
      (footprint "eagle-import:HEADER_MALE_01")
      (fields (field (name "SPICEPREFIX") "X"))
      (libsource (lib "eagle-import") (part "HEADER/MALE/01"))
    )
    (comp (ref "TNSY_22")
      (value "HEADER/MALE/01")
      (footprint "eagle-import:HEADER_MALE_01")
      (fields (field (name "SPICEPREFIX") "X"))
      (libsource (lib "eagle-import") (part "HEADER/MALE/01"))
    )
    (comp (ref "TNSY_23")
      (value "HEADER/MALE/01")
      (footprint "eagle-import:HEADER_MALE_01")
      (fields (field (name "SPICEPREFIX") "X"))
      (libsource (lib "eagle-import") (part "HEADER/MALE/01"))
    )
    (comp (ref "TNSY_CS")
      (value "HEADER/MALE/01")
      (footprint "eagle-import:HEADER_MALE_01")
      (fields (field (name "SPICEPREFIX") "X"))
      (libsource (lib "eagle-import") (part "HEADER/MALE/01"))
    )
    (comp (ref "TNSY_GND")
      (value "HEADER/MALE/01")
      (footprint "eagle-import:HEADER_MALE_01")
      (fields (field (name "SPICEPREFIX") "X"))
      (libsource (lib "eagle-import") (part "HEADER/MALE/01"))
    )
    (comp (ref "TNSY_GND2")
      (value "HEADER/MALE/01")
      (footprint "eagle-import:HEADER_MALE_01")
      (fields (field (name "SPICEPREFIX") "X"))
      (libsource (lib "eagle-import") (part "HEADER/MALE/01"))
    )
    (comp (ref "TNSY_MISO")
      (value "HEADER/MALE/01")
      (footprint "eagle-import:HEADER_MALE_01")
      (fields (field (name "SPICEPREFIX") "X"))
      (libsource (lib "eagle-import") (part "HEADER/MALE/01"))
    )
    (comp (ref "TNSY_MOSI")
      (value "HEADER/MALE/01")
      (footprint "eagle-import:HEADER_MALE_01")
      (fields (field (name "SPICEPREFIX") "X"))
      (libsource (lib "eagle-import") (part "HEADER/MALE/01"))
    )
    (comp (ref "TNSY_SCK")
      (value "HEADER/MALE/01")
      (footprint "eagle-import:HEADER_MALE_01")
      (fields (field (name "SPICEPREFIX") "X"))
      (libsource (lib "eagle-import") (part "HEADER/MALE/01"))
    )
    (comp (ref "TNSY_VIN")
      (value "HEADER/MALE/01")
      (footprint "eagle-import:HEADER_MALE_01")
      (fields (field (name "SPICEPREFIX") "X"))
      (libsource (lib "eagle-import") (part "HEADER/MALE/01"))
    )
  )
  (nets
    (net (code "1") (name "+5V") (class "Default")
      (node (ref "5V") (pin "1") (pinfunction "3_1") (pintype "passive"))
      (node (ref "C3") (pin "+") (pinfunction "+_+") (pintype "passive"))
      (node (ref "IC2") (pin "3") (pinfunction "VO_3") (pintype "passive"))
      (node (ref "PIXI_5V") (pin "1") (pinfunction "3_1") (pintype "passive"))
      (node (ref "TNSY_VIN") (pin "1") (pinfunction "3_1") (pintype "passive"))
    )
    (net (code "2") (name "+12V") (class "Default")
      (node (ref "+V") (pin "1") (pinfunction "3_1") (pintype "passive"))
      (node (ref "+V2") (pin "1") (pinfunction "3_1") (pintype "passive"))
      (node (ref "+V3") (pin "1") (pinfunction "3_1") (pintype "passive"))
      (node (ref "C1") (pin "+") (pinfunction "+_+") (pintype "passive"))
      (node (ref "IC2") (pin "1") (pinfunction "VI_1") (pintype "input"))
      (node (ref "R21") (pin "2") (pinfunction "2_2") (pintype "passive"))
    )
    (net (code "3") (name "-12V") (class "Default")
      (node (ref "-V") (pin "1") (pinfunction "3_1") (pintype "passive"))
      (node (ref "-V2") (pin "1") (pinfunction "3_1") (pintype "passive"))
      (node (ref "-V3") (pin "1") (pinfunction "3_1") (pintype "passive"))
      (node (ref "C2") (pin "-") (pinfunction "-_-") (pintype "passive"))
      (node (ref "R22") (pin "2") (pinfunction "2_2") (pintype "passive"))
    )
    (net (code "4") (name "GND") (class "Default")
      (node (ref "C1") (pin "-") (pinfunction "-_-") (pintype "passive"))
      (node (ref "C2") (pin "+") (pinfunction "+_+") (pintype "passive"))
      (node (ref "C3") (pin "-") (pinfunction "-_-") (pintype "passive"))
      (node (ref "D1") (pin "C") (pinfunction "C_C") (pintype "passive"))
      (node (ref "D2") (pin "A") (pinfunction "A_A") (pintype "passive"))
      (node (ref "GND") (pin "1") (pinfunction "3_1") (pintype "passive"))
      (node (ref "GND2") (pin "1") (pinfunction "3_1") (pintype "passive"))
      (node (ref "GND3") (pin "1") (pinfunction "3_1") (pintype "passive"))
      (node (ref "IC2") (pin "2") (pinfunction "GND_2") (pintype "passive"))
      (node (ref "PIXI_GND") (pin "1") (pinfunction "3_1") (pintype "passive"))
      (node (ref "PIXI_GND2") (pin "1") (pinfunction "3_1") (pintype "passive"))
      (node (ref "TNSY_GND") (pin "1") (pinfunction "3_1") (pintype "passive"))
    )
    (net (code "5") (name "Net-(0-3)") (class "Default")
      (node (ref "0") (pin "1") (pinfunction "3_1") (pintype "passive"))
      (node (ref "TNSY_0") (pin "1") (pinfunction "3_1") (pintype "passive"))
    )
    (net (code "6") (name "Net-(1-3)") (class "Default")
      (node (ref "1") (pin "1") (pinfunction "3_1") (pintype "passive"))
      (node (ref "TNSY_1") (pin "1") (pinfunction "3_1") (pintype "passive"))
    )
    (net (code "7") (name "Net-(2-3)") (class "Default")
      (node (ref "2") (pin "1") (pinfunction "3_1") (pintype "passive"))
      (node (ref "TNSY_2") (pin "1") (pinfunction "3_1") (pintype "passive"))
    )
    (net (code "8") (name "Net-(3-3)") (class "Default")
      (node (ref "3") (pin "1") (pinfunction "3_1") (pintype "passive"))
      (node (ref "TNSY_3") (pin "1") (pinfunction "3_1") (pintype "passive"))
    )
    (net (code "9") (name "Net-(3.3V-3)") (class "Default")
      (node (ref "3.3V") (pin "1") (pinfunction "3_1") (pintype "passive"))
      (node (ref "PIXI_3.3V") (pin "1") (pinfunction "3_1") (pintype "passive"))
      (node (ref "TNSY_3.3V") (pin "1") (pinfunction "3_1") (pintype "passive"))
    )
    (net (code "10") (name "Net-(4-3)") (class "Default")
      (node (ref "4") (pin "1") (pinfunction "3_1") (pintype "passive"))
      (node (ref "TNSY_4") (pin "1") (pinfunction "3_1") (pintype "passive"))
    )
    (net (code "11") (name "Net-(5-3)") (class "Default")
      (node (ref "5") (pin "1") (pinfunction "3_1") (pintype "passive"))
      (node (ref "TNSY_5") (pin "1") (pinfunction "3_1") (pintype "passive"))
    )
    (net (code "12") (name "Net-(6-3)") (class "Default")
      (node (ref "6") (pin "1") (pinfunction "3_1") (pintype "passive"))
      (node (ref "TNSY_6") (pin "1") (pinfunction "3_1") (pintype "passive"))
    )
    (net (code "13") (name "Net-(7-3)") (class "Default")
      (node (ref "7") (pin "1") (pinfunction "3_1") (pintype "passive"))
      (node (ref "TNSY_7") (pin "1") (pinfunction "3_1") (pintype "passive"))
    )
    (net (code "14") (name "Net-(8-3)") (class "Default")
      (node (ref "8") (pin "1") (pinfunction "3_1") (pintype "passive"))
      (node (ref "TNSY_8") (pin "1") (pinfunction "3_1") (pintype "passive"))
    )
    (net (code "15") (name "Net-(9-3)") (class "Default")
      (node (ref "9") (pin "1") (pinfunction "3_1") (pintype "passive"))
      (node (ref "TNSY_9") (pin "1") (pinfunction "3_1") (pintype "passive"))
    )
    (net (code "16") (name "Net-(16-3)") (class "Default")
      (node (ref "16") (pin "1") (pinfunction "3_1") (pintype "passive"))
      (node (ref "TNSY_16") (pin "1") (pinfunction "3_1") (pintype "passive"))
    )
    (net (code "17") (name "Net-(17-3)") (class "Default")
      (node (ref "17") (pin "1") (pinfunction "3_1") (pintype "passive"))
      (node (ref "TNSY_17") (pin "1") (pinfunction "3_1") (pintype "passive"))
    )
    (net (code "18") (name "Net-(18-3)") (class "Default")
      (node (ref "18") (pin "1") (pinfunction "3_1") (pintype "passive"))
      (node (ref "TNSY_18") (pin "1") (pinfunction "3_1") (pintype "passive"))
    )
    (net (code "19") (name "Net-(19-3)") (class "Default")
      (node (ref "19") (pin "1") (pinfunction "3_1") (pintype "passive"))
      (node (ref "TNSY_19") (pin "1") (pinfunction "3_1") (pintype "passive"))
    )
    (net (code "20") (name "Net-(20-3)") (class "Default")
      (node (ref "20") (pin "1") (pinfunction "3_1") (pintype "passive"))
      (node (ref "TNSY_20") (pin "1") (pinfunction "3_1") (pintype "passive"))
    )
    (net (code "21") (name "Net-(21-3)") (class "Default")
      (node (ref "21") (pin "1") (pinfunction "3_1") (pintype "passive"))
      (node (ref "TNSY_21") (pin "1") (pinfunction "3_1") (pintype "passive"))
    )
    (net (code "22") (name "Net-(22-3)") (class "Default")
      (node (ref "22") (pin "1") (pinfunction "3_1") (pintype "passive"))
      (node (ref "TNSY_22") (pin "1") (pinfunction "3_1") (pintype "passive"))
    )
    (net (code "23") (name "Net-(23-3)") (class "Default")
      (node (ref "23") (pin "1") (pinfunction "3_1") (pintype "passive"))
      (node (ref "TNSY_23") (pin "1") (pinfunction "3_1") (pintype "passive"))
    )
    (net (code "24") (name "Net-(AVDDIO-3)") (class "Default")
      (node (ref "AVDDIO") (pin "1") (pinfunction "3_1") (pintype "passive"))
      (node (ref "D2") (pin "C") (pinfunction "C_C") (pintype "passive"))
      (node (ref "R21") (pin "1") (pinfunction "1_1") (pintype "passive"))
    )
    (net (code "25") (name "Net-(AVSSIO-3)") (class "Default")
      (node (ref "AVSSIO") (pin "1") (pinfunction "3_1") (pintype "passive"))
      (node (ref "D1") (pin "A") (pinfunction "A_A") (pintype "passive"))
      (node (ref "R22") (pin "1") (pinfunction "1_1") (pintype "passive"))
    )
    (net (code "26") (name "Net-(CNV-3)") (class "Default")
      (node (ref "CNV") (pin "1") (pinfunction "3_1") (pintype "passive"))
      (node (ref "PIXI_INT") (pin "1") (pinfunction "3_1") (pintype "passive"))
      (node (ref "TNSY_15") (pin "1") (pinfunction "3_1") (pintype "passive"))
    )
    (net (code "27") (name "Net-(INT-3)") (class "Default")
      (node (ref "INT") (pin "1") (pinfunction "3_1") (pintype "passive"))
      (node (ref "PIXI_CNV") (pin "1") (pinfunction "3_1") (pintype "passive"))
      (node (ref "TNSY_14") (pin "1") (pinfunction "3_1") (pintype "passive"))
    )
    (net (code "28") (name "Net-(IO_0-3)") (class "Default")
      (node (ref "IO_0") (pin "1") (pinfunction "3_1") (pintype "passive"))
      (node (ref "IO__0") (pin "1") (pinfunction "3_1") (pintype "passive"))
      (node (ref "R1") (pin "2") (pinfunction "2_2") (pintype "passive"))
    )
    (net (code "29") (name "Net-(IO_1-3)") (class "Default")
      (node (ref "IO_1") (pin "1") (pinfunction "3_1") (pintype "passive"))
      (node (ref "IO__1") (pin "1") (pinfunction "3_1") (pintype "passive"))
      (node (ref "R2") (pin "2") (pinfunction "2_2") (pintype "passive"))
    )
    (net (code "30") (name "Net-(IO_2-3)") (class "Default")
      (node (ref "IO_2") (pin "1") (pinfunction "3_1") (pintype "passive"))
      (node (ref "IO__2") (pin "1") (pinfunction "3_1") (pintype "passive"))
      (node (ref "R3") (pin "2") (pinfunction "2_2") (pintype "passive"))
    )
    (net (code "31") (name "Net-(IO_3-3)") (class "Default")
      (node (ref "IO_3") (pin "1") (pinfunction "3_1") (pintype "passive"))
      (node (ref "IO__3") (pin "1") (pinfunction "3_1") (pintype "passive"))
      (node (ref "R4") (pin "2") (pinfunction "2_2") (pintype "passive"))
    )
    (net (code "32") (name "Net-(IO_4-3)") (class "Default")
      (node (ref "IO_4") (pin "1") (pinfunction "3_1") (pintype "passive"))
      (node (ref "IO__4") (pin "1") (pinfunction "3_1") (pintype "passive"))
      (node (ref "R5") (pin "2") (pinfunction "2_2") (pintype "passive"))
    )
    (net (code "33") (name "Net-(IO_5-3)") (class "Default")
      (node (ref "IO_5") (pin "1") (pinfunction "3_1") (pintype "passive"))
      (node (ref "IO__5") (pin "1") (pinfunction "3_1") (pintype "passive"))
      (node (ref "R6") (pin "2") (pinfunction "2_2") (pintype "passive"))
    )
    (net (code "34") (name "Net-(IO_6-3)") (class "Default")
      (node (ref "IO_6") (pin "1") (pinfunction "3_1") (pintype "passive"))
      (node (ref "IO__6") (pin "1") (pinfunction "3_1") (pintype "passive"))
      (node (ref "R7") (pin "2") (pinfunction "2_2") (pintype "passive"))
    )
    (net (code "35") (name "Net-(IO_7-3)") (class "Default")
      (node (ref "IO_7") (pin "1") (pinfunction "3_1") (pintype "passive"))
      (node (ref "IO__7") (pin "1") (pinfunction "3_1") (pintype "passive"))
      (node (ref "R8") (pin "2") (pinfunction "2_2") (pintype "passive"))
    )
    (net (code "36") (name "Net-(IO_8-3)") (class "Default")
      (node (ref "IO_8") (pin "1") (pinfunction "3_1") (pintype "passive"))
      (node (ref "IO__8") (pin "1") (pinfunction "3_1") (pintype "passive"))
      (node (ref "R9") (pin "2") (pinfunction "2_2") (pintype "passive"))
    )
    (net (code "37") (name "Net-(IO_9-3)") (class "Default")
      (node (ref "IO_9") (pin "1") (pinfunction "3_1") (pintype "passive"))
      (node (ref "IO__9") (pin "1") (pinfunction "3_1") (pintype "passive"))
      (node (ref "R10") (pin "2") (pinfunction "2_2") (pintype "passive"))
    )
    (net (code "38") (name "Net-(IO_10-3)") (class "Default")
      (node (ref "IO_10") (pin "1") (pinfunction "3_1") (pintype "passive"))
      (node (ref "IO__10") (pin "1") (pinfunction "3_1") (pintype "passive"))
      (node (ref "R11") (pin "2") (pinfunction "2_2") (pintype "passive"))
    )
    (net (code "39") (name "Net-(IO_11-3)") (class "Default")
      (node (ref "IO_11") (pin "1") (pinfunction "3_1") (pintype "passive"))
      (node (ref "IO__11") (pin "1") (pinfunction "3_1") (pintype "passive"))
      (node (ref "R12") (pin "2") (pinfunction "2_2") (pintype "passive"))
    )
    (net (code "40") (name "Net-(IO_12-3)") (class "Default")
      (node (ref "IO_12") (pin "1") (pinfunction "3_1") (pintype "passive"))
      (node (ref "IO__12") (pin "1") (pinfunction "3_1") (pintype "passive"))
      (node (ref "R13") (pin "2") (pinfunction "2_2") (pintype "passive"))
    )
    (net (code "41") (name "Net-(IO_13-3)") (class "Default")
      (node (ref "IO_13") (pin "1") (pinfunction "3_1") (pintype "passive"))
      (node (ref "IO__13") (pin "1") (pinfunction "3_1") (pintype "passive"))
      (node (ref "R14") (pin "2") (pinfunction "2_2") (pintype "passive"))
    )
    (net (code "42") (name "Net-(IO_14-3)") (class "Default")
      (node (ref "IO_14") (pin "1") (pinfunction "3_1") (pintype "passive"))
      (node (ref "IO__14") (pin "1") (pinfunction "3_1") (pintype "passive"))
      (node (ref "R15") (pin "2") (pinfunction "2_2") (pintype "passive"))
    )
    (net (code "43") (name "Net-(IO_15-3)") (class "Default")
      (node (ref "IO_15") (pin "1") (pinfunction "3_1") (pintype "passive"))
      (node (ref "IO__15") (pin "1") (pinfunction "3_1") (pintype "passive"))
      (node (ref "R16") (pin "2") (pinfunction "2_2") (pintype "passive"))
    )
    (net (code "44") (name "Net-(IO_16-3)") (class "Default")
      (node (ref "IO_16") (pin "1") (pinfunction "3_1") (pintype "passive"))
      (node (ref "IO__16") (pin "1") (pinfunction "3_1") (pintype "passive"))
      (node (ref "R17") (pin "2") (pinfunction "2_2") (pintype "passive"))
    )
    (net (code "45") (name "Net-(IO_17-3)") (class "Default")
      (node (ref "IO_17") (pin "1") (pinfunction "3_1") (pintype "passive"))
      (node (ref "IO__17") (pin "1") (pinfunction "3_1") (pintype "passive"))
      (node (ref "R18") (pin "2") (pinfunction "2_2") (pintype "passive"))
    )
    (net (code "46") (name "Net-(IO_18-3)") (class "Default")
      (node (ref "IO_18") (pin "1") (pinfunction "3_1") (pintype "passive"))
      (node (ref "IO__18") (pin "1") (pinfunction "3_1") (pintype "passive"))
      (node (ref "R19") (pin "2") (pinfunction "2_2") (pintype "passive"))
    )
    (net (code "47") (name "Net-(IO_19-3)") (class "Default")
      (node (ref "IO_19") (pin "1") (pinfunction "3_1") (pintype "passive"))
      (node (ref "IO__19") (pin "1") (pinfunction "3_1") (pintype "passive"))
      (node (ref "R20") (pin "2") (pinfunction "2_2") (pintype "passive"))
    )
    (net (code "48") (name "Net-(MISO-3)") (class "Default")
      (node (ref "MISO") (pin "1") (pinfunction "3_1") (pintype "passive"))
      (node (ref "PIXI_SDO") (pin "1") (pinfunction "3_1") (pintype "passive"))
      (node (ref "TNSY_MISO") (pin "1") (pinfunction "3_1") (pintype "passive"))
    )
    (net (code "49") (name "Net-(MOSI-3)") (class "Default")
      (node (ref "MOSI") (pin "1") (pinfunction "3_1") (pintype "passive"))
      (node (ref "PIXI_SDI") (pin "1") (pinfunction "3_1") (pintype "passive"))
      (node (ref "TNSY_MOSI") (pin "1") (pinfunction "3_1") (pintype "passive"))
    )
    (net (code "50") (name "Net-(PIXI_0-3)") (class "Default")
      (node (ref "PIXI_0") (pin "1") (pinfunction "3_1") (pintype "passive"))
      (node (ref "R1") (pin "1") (pinfunction "1_1") (pintype "passive"))
    )
    (net (code "51") (name "Net-(PIXI_1-3)") (class "Default")
      (node (ref "PIXI_1") (pin "1") (pinfunction "3_1") (pintype "passive"))
      (node (ref "R2") (pin "1") (pinfunction "1_1") (pintype "passive"))
    )
    (net (code "52") (name "Net-(PIXI_2-3)") (class "Default")
      (node (ref "PIXI_2") (pin "1") (pinfunction "3_1") (pintype "passive"))
      (node (ref "R3") (pin "1") (pinfunction "1_1") (pintype "passive"))
    )
    (net (code "53") (name "Net-(PIXI_3-3)") (class "Default")
      (node (ref "PIXI_3") (pin "1") (pinfunction "3_1") (pintype "passive"))
      (node (ref "R4") (pin "1") (pinfunction "1_1") (pintype "passive"))
    )
    (net (code "54") (name "Net-(PIXI_4-3)") (class "Default")
      (node (ref "PIXI_4") (pin "1") (pinfunction "3_1") (pintype "passive"))
      (node (ref "R5") (pin "1") (pinfunction "1_1") (pintype "passive"))
    )
    (net (code "55") (name "Net-(PIXI_5-3)") (class "Default")
      (node (ref "PIXI_5") (pin "1") (pinfunction "3_1") (pintype "passive"))
      (node (ref "R6") (pin "1") (pinfunction "1_1") (pintype "passive"))
    )
    (net (code "56") (name "Net-(PIXI_6-3)") (class "Default")
      (node (ref "PIXI_6") (pin "1") (pinfunction "3_1") (pintype "passive"))
      (node (ref "R7") (pin "1") (pinfunction "1_1") (pintype "passive"))
    )
    (net (code "57") (name "Net-(PIXI_7-3)") (class "Default")
      (node (ref "PIXI_7") (pin "1") (pinfunction "3_1") (pintype "passive"))
      (node (ref "R8") (pin "1") (pinfunction "1_1") (pintype "passive"))
    )
    (net (code "58") (name "Net-(PIXI_8-3)") (class "Default")
      (node (ref "PIXI_8") (pin "1") (pinfunction "3_1") (pintype "passive"))
      (node (ref "R9") (pin "1") (pinfunction "1_1") (pintype "passive"))
    )
    (net (code "59") (name "Net-(PIXI_9-3)") (class "Default")
      (node (ref "PIXI_9") (pin "1") (pinfunction "3_1") (pintype "passive"))
      (node (ref "R10") (pin "1") (pinfunction "1_1") (pintype "passive"))
    )
    (net (code "60") (name "Net-(PIXI_10-3)") (class "Default")
      (node (ref "PIXI_10") (pin "1") (pinfunction "3_1") (pintype "passive"))
      (node (ref "R11") (pin "1") (pinfunction "1_1") (pintype "passive"))
    )
    (net (code "61") (name "Net-(PIXI_11-3)") (class "Default")
      (node (ref "PIXI_11") (pin "1") (pinfunction "3_1") (pintype "passive"))
      (node (ref "R12") (pin "1") (pinfunction "1_1") (pintype "passive"))
    )
    (net (code "62") (name "Net-(PIXI_12-3)") (class "Default")
      (node (ref "PIXI_12") (pin "1") (pinfunction "3_1") (pintype "passive"))
      (node (ref "R13") (pin "1") (pinfunction "1_1") (pintype "passive"))
    )
    (net (code "63") (name "Net-(PIXI_13-3)") (class "Default")
      (node (ref "PIXI_13") (pin "1") (pinfunction "3_1") (pintype "passive"))
      (node (ref "R14") (pin "1") (pinfunction "1_1") (pintype "passive"))
    )
    (net (code "64") (name "Net-(PIXI_14-3)") (class "Default")
      (node (ref "PIXI_14") (pin "1") (pinfunction "3_1") (pintype "passive"))
      (node (ref "R15") (pin "1") (pinfunction "1_1") (pintype "passive"))
    )
    (net (code "65") (name "Net-(PIXI_15-3)") (class "Default")
      (node (ref "PIXI_15") (pin "1") (pinfunction "3_1") (pintype "passive"))
      (node (ref "R16") (pin "1") (pinfunction "1_1") (pintype "passive"))
    )
    (net (code "66") (name "Net-(PIXI_16-3)") (class "Default")
      (node (ref "PIXI_16") (pin "1") (pinfunction "3_1") (pintype "passive"))
      (node (ref "R17") (pin "1") (pinfunction "1_1") (pintype "passive"))
    )
    (net (code "67") (name "Net-(PIXI_17-3)") (class "Default")
      (node (ref "PIXI_17") (pin "1") (pinfunction "3_1") (pintype "passive"))
      (node (ref "R18") (pin "1") (pinfunction "1_1") (pintype "passive"))
    )
    (net (code "68") (name "Net-(PIXI_18-3)") (class "Default")
      (node (ref "PIXI_18") (pin "1") (pinfunction "3_1") (pintype "passive"))
      (node (ref "R19") (pin "1") (pinfunction "1_1") (pintype "passive"))
    )
    (net (code "69") (name "Net-(PIXI_19-3)") (class "Default")
      (node (ref "PIXI_19") (pin "1") (pinfunction "3_1") (pintype "passive"))
      (node (ref "R20") (pin "1") (pinfunction "1_1") (pintype "passive"))
    )
    (net (code "70") (name "Net-(PIXI_CS-3)") (class "Default")
      (node (ref "PIXI_CS") (pin "1") (pinfunction "3_1") (pintype "passive"))
      (node (ref "TNSY_CS") (pin "1") (pinfunction "3_1") (pintype "passive"))
    )
    (net (code "71") (name "Net-(PIXI_SCK-3)") (class "Default")
      (node (ref "PIXI_SCK") (pin "1") (pinfunction "3_1") (pintype "passive"))
      (node (ref "SCK") (pin "1") (pinfunction "3_1") (pintype "passive"))
      (node (ref "TNSY_SCK") (pin "1") (pinfunction "3_1") (pintype "passive"))
    )
    (net (code "72") (name "unconnected-(PIXI_NC1-3-Pad1)") (class "Default")
      (node (ref "PIXI_NC1") (pin "1") (pinfunction "3_1") (pintype "passive"))
    )
    (net (code "73") (name "unconnected-(PIXI_NC2-3-Pad1)") (class "Default")
      (node (ref "PIXI_NC2") (pin "1") (pinfunction "3_1") (pintype "passive"))
    )
    (net (code "74") (name "unconnected-(PIXI_NC3-3-Pad1)") (class "Default")
      (node (ref "PIXI_NC3") (pin "1") (pinfunction "3_1") (pintype "passive"))
    )
    (net (code "75") (name "unconnected-(PIXI_NC4-3-Pad1)") (class "Default")
      (node (ref "PIXI_NC4") (pin "1") (pinfunction "3_1") (pintype "passive"))
    )
    (net (code "76") (name "unconnected-(PIXI_NC5-3-Pad1)") (class "Default")
      (node (ref "PIXI_NC5") (pin "1") (pinfunction "3_1") (pintype "passive"))
    )
    (net (code "77") (name "unconnected-(PIXI_NC6-3-Pad1)") (class "Default")
      (node (ref "PIXI_NC6") (pin "1") (pinfunction "3_1") (pintype "passive"))
    )
    (net (code "78") (name "unconnected-(TNSY_GND2-3-Pad1)") (class "Default")
      (node (ref "TNSY_GND2") (pin "1") (pinfunction "3_1") (pintype "passive"))
    )
  )
)
